# Julia_ABL_Board_V2_1.net
KiCad netlist of a schematic drawn in EAGLE
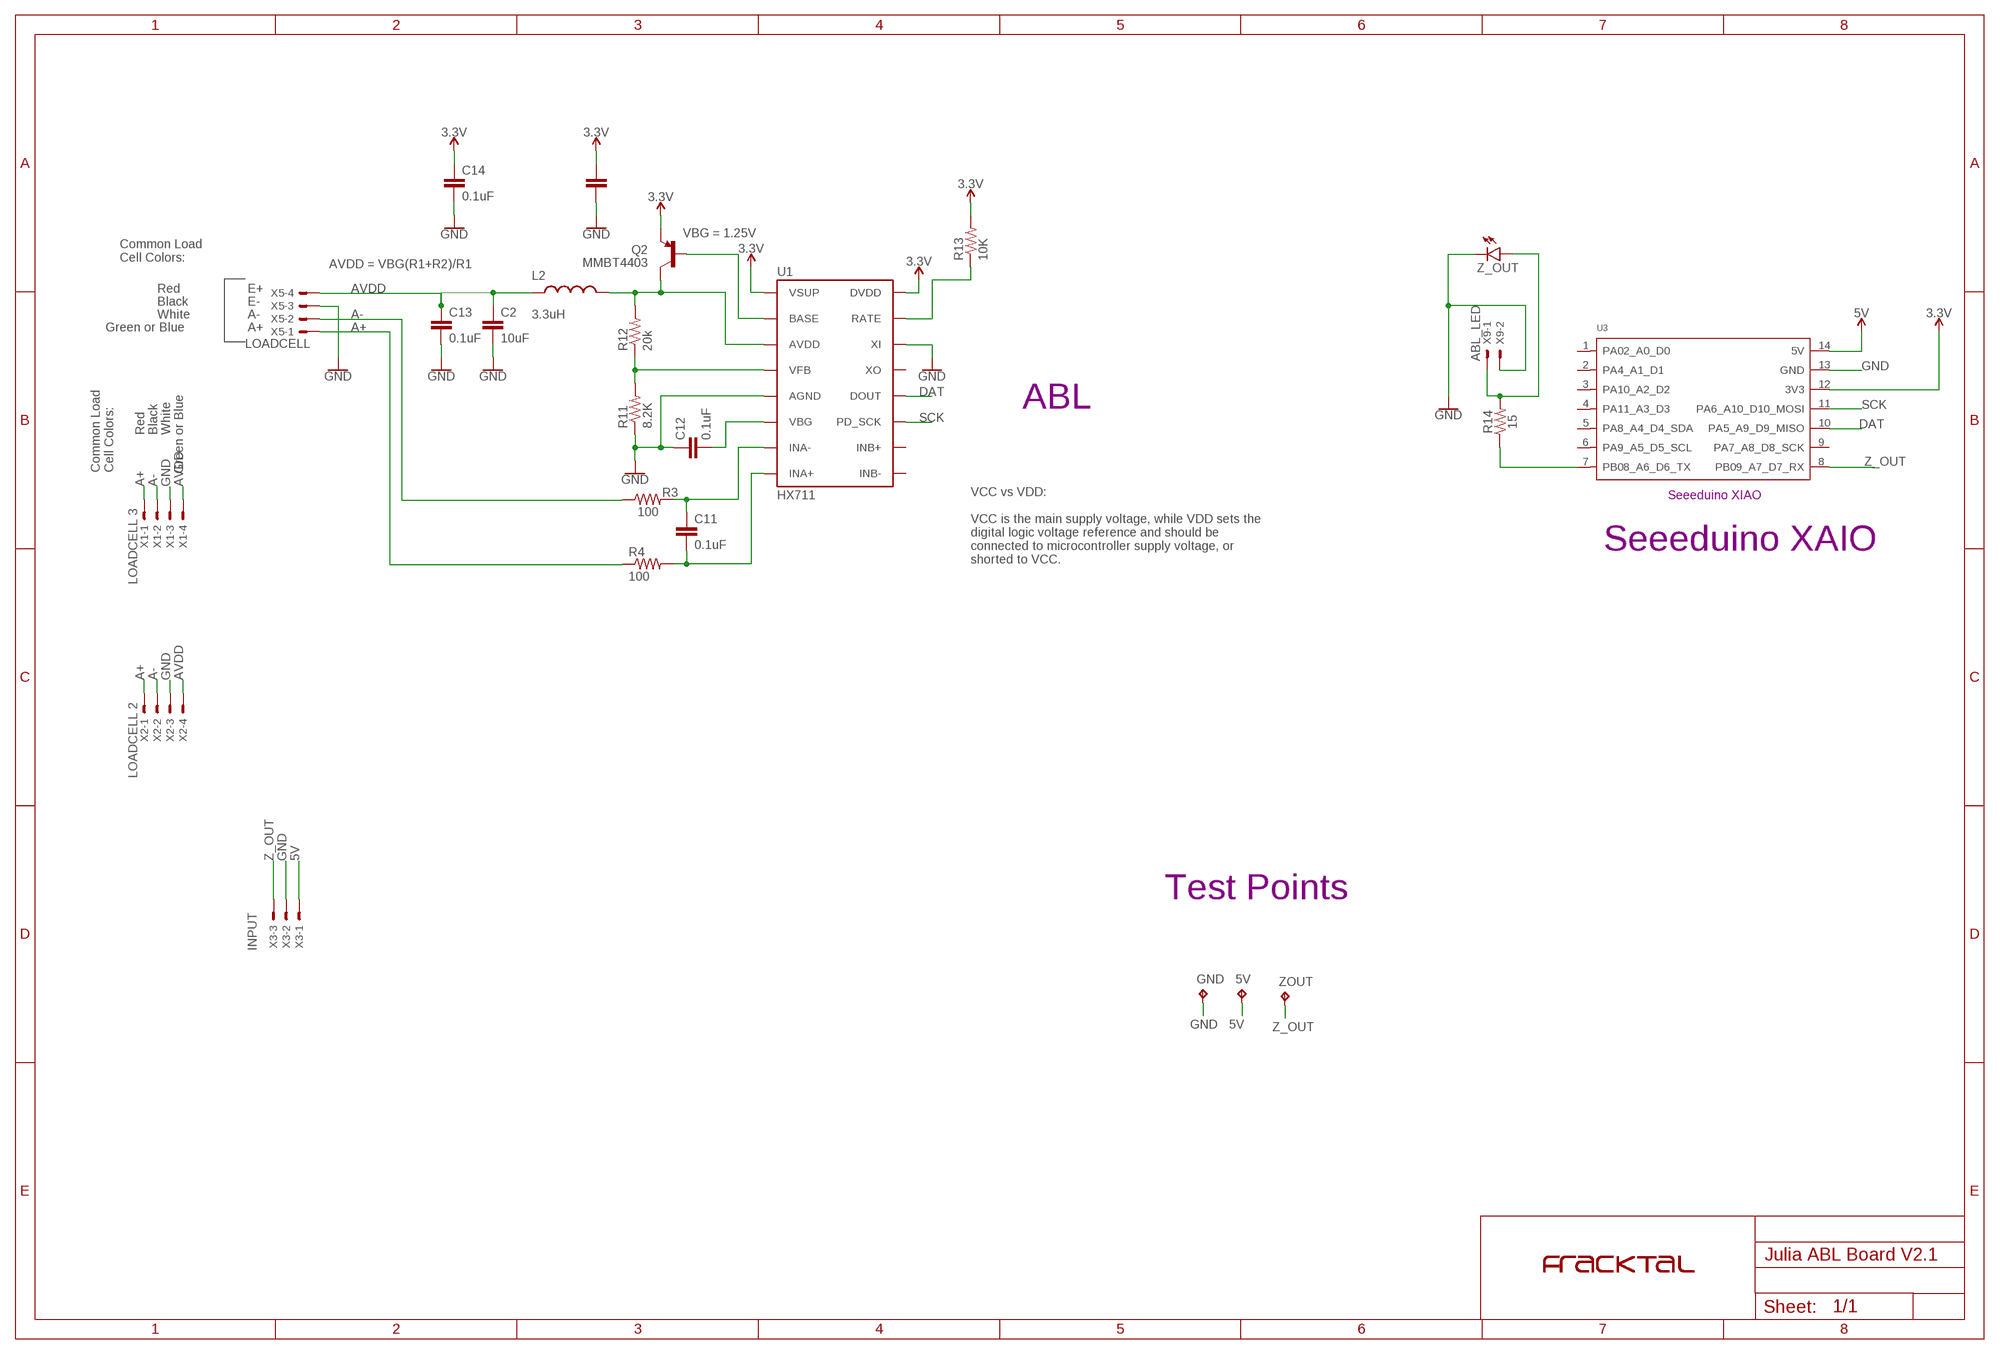
[diagram p0: schematic, sheet 1]

(export (version "E")
  (design (tool "Eeschema 10.0.6"))
  (components
    (comp (ref "5V")
      (value "TPB2,54")
      (footprint "eagle-import:B2,54")
      (libsource (lib "eagle-import") (part "TPB2,54"))
    )
    (comp (ref "C1")
      (value "10uF")
      (footprint "eagle-import:1210")
      (libsource (lib "eagle-import") (part "10UF50V20%(1210)"))
    )
    (comp (ref "C2")
      (value "10uF")
      (footprint "eagle-import:1210")
      (libsource (lib "eagle-import") (part "10UF50V20%(1210)"))
    )
    (comp (ref "C11")
      (value "0.1uF")
      (footprint "eagle-import:0603-CAP")
      (libsource (lib "eagle-import") (part "0.1UF-25V-5%(0603)"))
    )
    (comp (ref "C12")
      (value "0.1uF")
      (footprint "eagle-import:0603-CAP")
      (libsource (lib "eagle-import") (part "0.1UF-25V-5%(0603)"))
    )
    (comp (ref "C13")
      (value "0.1uF")
      (footprint "eagle-import:0603-CAP")
      (libsource (lib "eagle-import") (part "0.1UF-25V-5%(0603)"))
    )
    (comp (ref "C14")
      (value "0.1uF")
      (footprint "eagle-import:0603-CAP")
      (libsource (lib "eagle-import") (part "0.1UF-25V-5%(0603)"))
    )
    (comp (ref "GND")
      (value "TPB2,54")
      (footprint "eagle-import:B2,54")
      (libsource (lib "eagle-import") (part "TPB2,54"))
    )
    (comp (ref "L2")
      (value "3.3uH")
      (footprint "eagle-import:0805")
      (libsource (lib "eagle-import") (part "INDUCTOR0805-IND"))
    )
    (comp (ref "Q2")
      (value "MMBT4403")
      (footprint "eagle-import:SOT23-3")
      (libsource (lib "eagle-import") (part "TRANSISTOR_PNPMMBT4403"))
    )
    (comp (ref "R3")
      (value "100")
      (footprint "eagle-import:0603-RES")
      (libsource (lib "eagle-import") (part "100OHM-1/10W-1%(0603)"))
    )
    (comp (ref "R4")
      (value "100")
      (footprint "eagle-import:0603-RES")
      (libsource (lib "eagle-import") (part "100OHM-1/10W-1%(0603)"))
    )
    (comp (ref "R11")
      (value "8.2K")
      (footprint "eagle-import:0603-RES")
      (libsource (lib "eagle-import") (part "8.2KOHM-1/10W-5%(0603)"))
    )
    (comp (ref "R12")
      (value "20k")
      (footprint "eagle-import:0603-RES")
      (libsource (lib "eagle-import") (part "20KOHM1/10W1%(0603)"))
    )
    (comp (ref "R13")
      (value "10K")
      (footprint "eagle-import:0603-RES")
      (libsource (lib "eagle-import") (part "10KOHM-1/10W-1%(0603)0603"))
    )
    (comp (ref "R14")
      (value "15")
      (footprint "eagle-import:0603")
      (libsource (lib "eagle-import") (part "RESISTOR0603"))
    )
    (comp (ref "U$2")
      (value "FRACKTALLOGO")
      (footprint "eagle-import:FRACKTALLOGO")
      (libsource (lib "eagle-import") (part "FRACKTALLOGO"))
    )
    (comp (ref "U1")
      (value "HX711")
      (footprint "eagle-import:SO16")
      (libsource (lib "eagle-import") (part "HX711HX711"))
    )
    (comp (ref "U3")
      (value "MOUDLE-SEEEDUINO-XIAO")
      (footprint "eagle-import:MOUDLE14P-2.54-21X17.8MM")
      (libsource (lib "eagle-import") (part "MOUDLE-SEEEDUINO-XIAO"))
    )
    (comp (ref "X1")
      (value "LOADCELL 3")
      (footprint "eagle-import:JST-XH-04-PACKAGE-LONG-PAD")
      (libsource (lib "eagle-import") (part "JST-XH-04-PIN-LONG-PAD"))
    )
    (comp (ref "X2")
      (value "LOADCELL 2")
      (footprint "eagle-import:JST-XH-04-PACKAGE-LONG-PAD")
      (libsource (lib "eagle-import") (part "JST-XH-04-PIN-LONG-PAD"))
    )
    (comp (ref "X3")
      (value "JST-XH-03-PIN-LONG-PAD")
      (footprint "eagle-import:JST-XH-03-PACKAGE-LONG-PAD")
      (fields (field (name "VALUE1") "INPUT"))
      (libsource (lib "eagle-import") (part "JST-XH-03-PIN-LONG-PAD"))
    )
    (comp (ref "X5")
      (value "LOADCELL")
      (footprint "eagle-import:JST-XH-04-PACKAGE-LONG-PAD")
      (libsource (lib "eagle-import") (part "JST-XH-04-PIN-LONG-PAD"))
    )
    (comp (ref "X9")
      (value "ABL_LED")
      (footprint "eagle-import:JST-XH-02-PACKAGE-LONG-PAD")
      (libsource (lib "eagle-import") (part "JST-XH-02-PIN-LONG-PAD"))
    )
    (comp (ref "ZOUT")
      (value "TPB2,54")
      (footprint "eagle-import:B2,54")
      (libsource (lib "eagle-import") (part "TPB2,54"))
    )
    (comp (ref "Z_OUT")
      (value "LEDSML0603")
      (footprint "eagle-import:SML0603")
      (libsource (lib "eagle-import") (part "LEDSML0603"))
    )
  )
  (nets
    (net (code "1") (name "/A+") (class "Default")
      (node (ref "R4") (pin "1") (pinfunction "1_1") (pintype "passive"))
      (node (ref "X1") (pin "1") (pinfunction "S_1") (pintype "passive"))
      (node (ref "X2") (pin "1") (pinfunction "S_1") (pintype "passive"))
      (node (ref "X5") (pin "1") (pinfunction "S_1") (pintype "passive"))
    )
    (net (code "2") (name "/A-") (class "Default")
      (node (ref "R3") (pin "1") (pinfunction "1_1") (pintype "passive"))
      (node (ref "X1") (pin "2") (pinfunction "S_2") (pintype "passive"))
      (node (ref "X2") (pin "2") (pinfunction "S_2") (pintype "passive"))
      (node (ref "X5") (pin "2") (pinfunction "S_2") (pintype "passive"))
    )
    (net (code "3") (name "/AVDD") (class "Default")
      (node (ref "C13") (pin "1") (pinfunction "1_1") (pintype "passive"))
      (node (ref "C2") (pin "1") (pinfunction "1_1") (pintype "passive"))
      (node (ref "L2") (pin "1") (pinfunction "1_1") (pintype "passive"))
      (node (ref "X1") (pin "4") (pinfunction "S_4") (pintype "passive"))
      (node (ref "X2") (pin "4") (pinfunction "S_4") (pintype "passive"))
      (node (ref "X5") (pin "4") (pinfunction "S_4") (pintype "passive"))
    )
    (net (code "4") (name "/DAT") (class "Default")
      (node (ref "U1") (pin "12") (pinfunction "DOUT_12") (pintype "bidirectional"))
      (node (ref "U3") (pin "10") (pinfunction "PA5_A9_D9_MISO_10") (pintype "bidirectional"))
    )
    (net (code "5") (name "/SCK") (class "Default")
      (node (ref "U1") (pin "11") (pinfunction "PD_SCK_11") (pintype "bidirectional"))
      (node (ref "U3") (pin "11") (pinfunction "PA6_A10_D10_MOSI_11") (pintype "bidirectional"))
    )
    (net (code "6") (name "/Z_OUT") (class "Default")
      (node (ref "U3") (pin "8") (pinfunction "PB09_A7_D7_RX_8") (pintype "bidirectional"))
      (node (ref "X3") (pin "3") (pinfunction "S_3") (pintype "passive"))
      (node (ref "ZOUT") (pin "TP") (pinfunction "TP_TP") (pintype "input"))
    )
    (net (code "7") (name "3.3V") (class "Default")
      (node (ref "C1") (pin "1") (pinfunction "1_1") (pintype "passive"))
      (node (ref "C14") (pin "1") (pinfunction "1_1") (pintype "passive"))
      (node (ref "Q2") (pin "2") (pinfunction "E_2") (pintype "passive"))
      (node (ref "R13") (pin "2") (pinfunction "2_2") (pintype "passive"))
      (node (ref "U1") (pin "1") (pinfunction "VSUP_1") (pintype "bidirectional"))
      (node (ref "U1") (pin "16") (pinfunction "DVDD_16") (pintype "bidirectional"))
      (node (ref "U3") (pin "12") (pinfunction "3V3_12") (pintype "bidirectional"))
    )
    (net (code "8") (name "5V") (class "Default")
      (node (ref "5V") (pin "TP") (pinfunction "TP_TP") (pintype "input"))
      (node (ref "U3") (pin "14") (pinfunction "5V_14") (pintype "bidirectional"))
      (node (ref "X3") (pin "1") (pinfunction "S_1") (pintype "passive"))
    )
    (net (code "9") (name "GND") (class "Default")
      (node (ref "C1") (pin "2") (pinfunction "2_2") (pintype "passive"))
      (node (ref "C12") (pin "1") (pinfunction "1_1") (pintype "passive"))
      (node (ref "C13") (pin "2") (pinfunction "2_2") (pintype "passive"))
      (node (ref "C14") (pin "2") (pinfunction "2_2") (pintype "passive"))
      (node (ref "C2") (pin "2") (pinfunction "2_2") (pintype "passive"))
      (node (ref "GND") (pin "TP") (pinfunction "TP_TP") (pintype "input"))
      (node (ref "R11") (pin "1") (pinfunction "1_1") (pintype "passive"))
      (node (ref "U1") (pin "14") (pinfunction "XI_14") (pintype "bidirectional"))
      (node (ref "U1") (pin "5") (pinfunction "AGND_5") (pintype "bidirectional"))
      (node (ref "U3") (pin "13") (pinfunction "GND_13") (pintype "bidirectional"))
      (node (ref "X1") (pin "3") (pinfunction "S_3") (pintype "passive"))
      (node (ref "X2") (pin "3") (pinfunction "S_3") (pintype "passive"))
      (node (ref "X3") (pin "2") (pinfunction "S_2") (pintype "passive"))
      (node (ref "X5") (pin "3") (pinfunction "S_3") (pintype "passive"))
      (node (ref "X9") (pin "2") (pinfunction "S_2") (pintype "passive"))
      (node (ref "Z_OUT") (pin "C") (pinfunction "C_C") (pintype "passive"))
    )
    (net (code "10") (name "Net-(Q2-B)") (class "Default")
      (node (ref "Q2") (pin "1") (pinfunction "B_1") (pintype "passive"))
      (node (ref "U1") (pin "2") (pinfunction "BASE_2") (pintype "bidirectional"))
    )
    (net (code "11") (name "Net-(Q2-C)") (class "Default")
      (node (ref "L2") (pin "2") (pinfunction "2_2") (pintype "passive"))
      (node (ref "Q2") (pin "3") (pinfunction "C_3") (pintype "passive"))
      (node (ref "R12") (pin "2") (pinfunction "2_2") (pintype "passive"))
      (node (ref "U1") (pin "3") (pinfunction "AVDD_3") (pintype "bidirectional"))
    )
    (net (code "12") (name "Net-(U1-INA+)") (class "Default")
      (node (ref "C11") (pin "2") (pinfunction "2_2") (pintype "passive"))
      (node (ref "R4") (pin "2") (pinfunction "2_2") (pintype "passive"))
      (node (ref "U1") (pin "8") (pinfunction "INA+_8") (pintype "bidirectional"))
    )
    (net (code "13") (name "Net-(U1-INA-)") (class "Default")
      (node (ref "C11") (pin "1") (pinfunction "1_1") (pintype "passive"))
      (node (ref "R3") (pin "2") (pinfunction "2_2") (pintype "passive"))
      (node (ref "U1") (pin "7") (pinfunction "INA-_7") (pintype "bidirectional"))
    )
    (net (code "14") (name "Net-(U1-RATE)") (class "Default")
      (node (ref "R13") (pin "1") (pinfunction "1_1") (pintype "passive"))
      (node (ref "U1") (pin "15") (pinfunction "RATE_15") (pintype "bidirectional"))
    )
    (net (code "15") (name "Net-(U1-VBG)") (class "Default")
      (node (ref "C12") (pin "2") (pinfunction "2_2") (pintype "passive"))
      (node (ref "U1") (pin "6") (pinfunction "VBG_6") (pintype "bidirectional"))
    )
    (net (code "16") (name "Net-(U1-VFB)") (class "Default")
      (node (ref "R11") (pin "2") (pinfunction "2_2") (pintype "passive"))
      (node (ref "R12") (pin "1") (pinfunction "1_1") (pintype "passive"))
      (node (ref "U1") (pin "4") (pinfunction "VFB_4") (pintype "bidirectional"))
    )
    (net (code "17") (name "Net-(U3-PB08_A6_D6_TX)") (class "Default")
      (node (ref "R14") (pin "1") (pinfunction "1_1") (pintype "passive"))
      (node (ref "U3") (pin "7") (pinfunction "PB08_A6_D6_TX_7") (pintype "bidirectional"))
    )
    (net (code "18") (name "Net-(X9A-S)") (class "Default")
      (node (ref "R14") (pin "2") (pinfunction "2_2") (pintype "passive"))
      (node (ref "X9") (pin "1") (pinfunction "S_1") (pintype "passive"))
      (node (ref "Z_OUT") (pin "A") (pinfunction "A_A") (pintype "passive"))
    )
    (net (code "19") (name "unconnected-(U1-INB+-Pad10)") (class "Default")
      (node (ref "U1") (pin "10") (pinfunction "INB+_10") (pintype "bidirectional"))
    )
    (net (code "20") (name "unconnected-(U1-INB--Pad9)") (class "Default")
      (node (ref "U1") (pin "9") (pinfunction "INB-_9") (pintype "bidirectional"))
    )
    (net (code "21") (name "unconnected-(U1-XO-Pad13)") (class "Default")
      (node (ref "U1") (pin "13") (pinfunction "XO_13") (pintype "bidirectional"))
    )
    (net (code "22") (name "unconnected-(U3-PA02_A0_D0-Pad1)") (class "Default")
      (node (ref "U3") (pin "1") (pinfunction "PA02_A0_D0_1") (pintype "bidirectional"))
    )
    (net (code "23") (name "unconnected-(U3-PA4_A1_D1-Pad2)") (class "Default")
      (node (ref "U3") (pin "2") (pinfunction "PA4_A1_D1_2") (pintype "bidirectional"))
    )
    (net (code "24") (name "unconnected-(U3-PA7_A8_D8_SCK-Pad9)") (class "Default")
      (node (ref "U3") (pin "9") (pinfunction "PA7_A8_D8_SCK_9") (pintype "bidirectional"))
    )
    (net (code "25") (name "unconnected-(U3-PA8_A4_D4_SDA-Pad5)") (class "Default")
      (node (ref "U3") (pin "5") (pinfunction "PA8_A4_D4_SDA_5") (pintype "bidirectional"))
    )
    (net (code "26") (name "unconnected-(U3-PA9_A5_D5_SCL-Pad6)") (class "Default")
      (node (ref "U3") (pin "6") (pinfunction "PA9_A5_D5_SCL_6") (pintype "bidirectional"))
    )
    (net (code "27") (name "unconnected-(U3-PA10_A2_D2-Pad3)") (class "Default")
      (node (ref "U3") (pin "3") (pinfunction "PA10_A2_D2_3") (pintype "bidirectional"))
    )
    (net (code "28") (name "unconnected-(U3-PA11_A3_D3-Pad4)") (class "Default")
      (node (ref "U3") (pin "4") (pinfunction "PA11_A3_D3_4") (pintype "bidirectional"))
    )
  )
)
